# SmartCanBus.net
KiCad netlist of a schematic drawn in Altium Designer
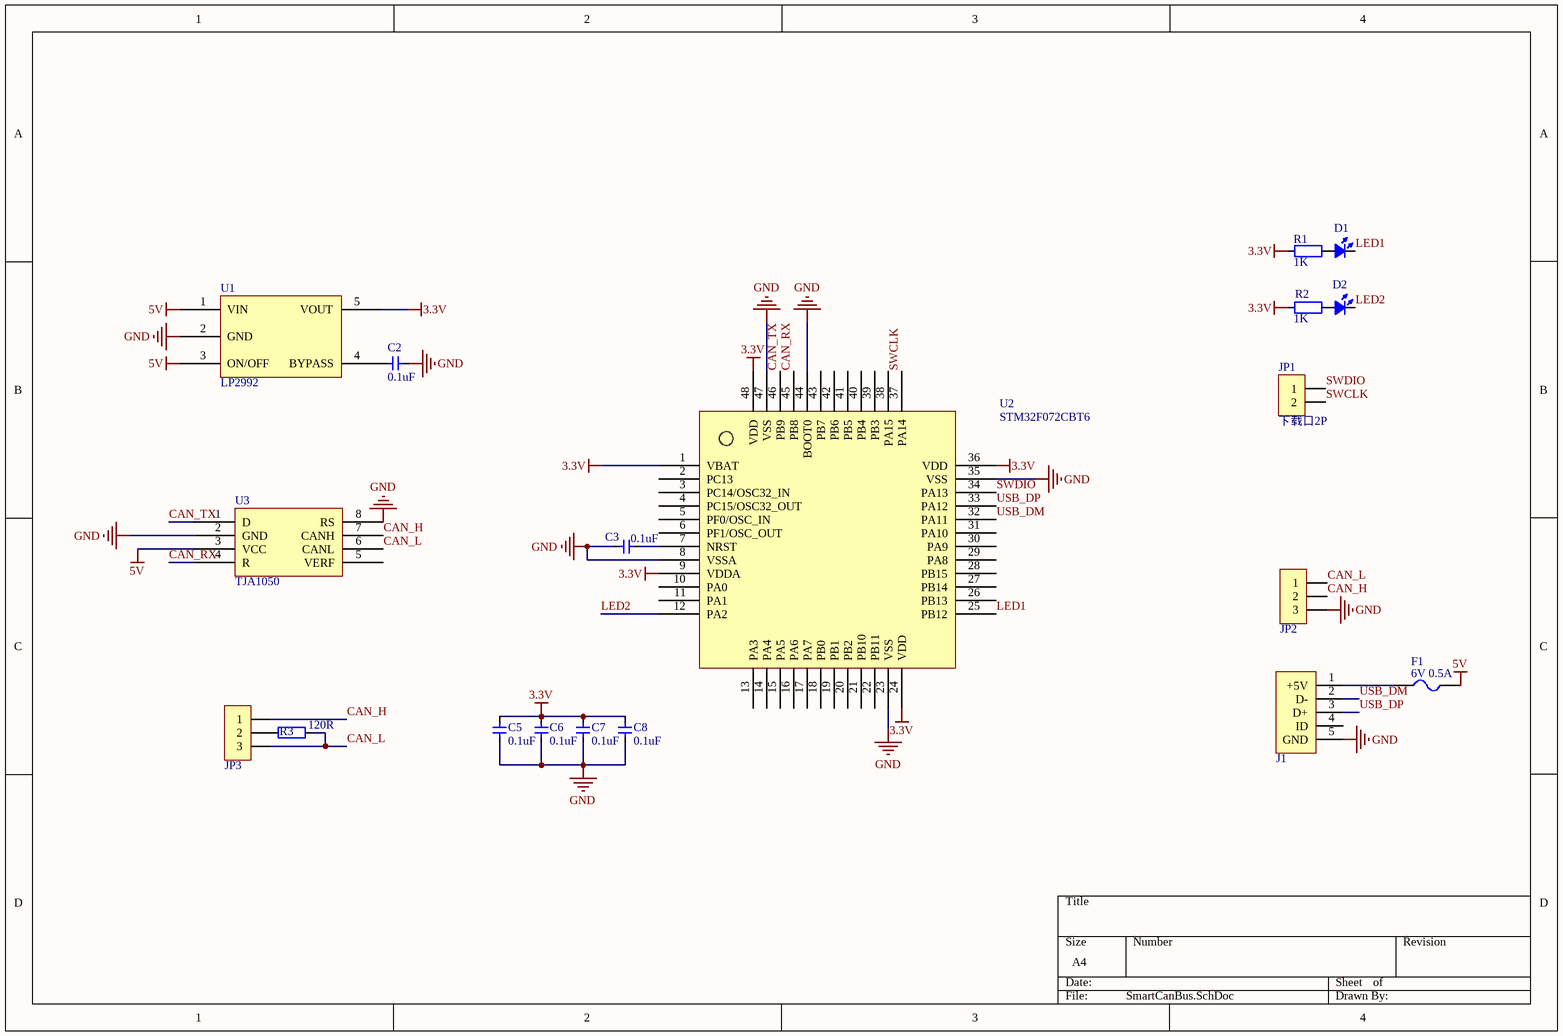
[diagram p0: SmartCanBus.SchDoc]

(export (version "E")
  (design (tool "Eeschema 10.0.6"))
  (components
    (comp (ref "C2")
      (value "0.1uF")
      (footprint "1.00-YltsPcbLib:0603_CAP")
      (description "电容")
      (libsource (lib "0.0 - YltsSchlib") (part "电容-0603"))
    )
    (comp (ref "C3")
      (value "0.1uF")
      (footprint "1.00-YltsPcbLib:0603_CAP")
      (description "电容")
      (libsource (lib "0.0 - YltsSchlib") (part "电容-0603"))
    )
    (comp (ref "C5")
      (value "0.1uF")
      (footprint "1.00-YltsPcbLib:0603_CAP")
      (description "电容")
      (libsource (lib "0.0 - YltsSchlib") (part "电容-0603"))
    )
    (comp (ref "C6")
      (value "0.1uF")
      (footprint "1.00-YltsPcbLib:0603_CAP")
      (description "电容")
      (libsource (lib "0.0 - YltsSchlib") (part "电容-0603"))
    )
    (comp (ref "C7")
      (value "0.1uF")
      (footprint "1.00-YltsPcbLib:0603_CAP")
      (description "电容")
      (libsource (lib "0.0 - YltsSchlib") (part "电容-0603"))
    )
    (comp (ref "C8")
      (value "0.1uF")
      (footprint "1.00-YltsPcbLib:0603_CAP")
      (description "电容")
      (libsource (lib "0.0 - YltsSchlib") (part "电容-0603"))
    )
    (comp (ref "D1")
      (value "LED-0603")
      (footprint "1.00-YltsPcbLib:0603_LED_RED")
      (description "发光二极管")
      (libsource (lib "0.0 - YltsSchlib") (part "二极管-0603-RED"))
    )
    (comp (ref "D2")
      (value "LED-0603")
      (footprint "1.00-YltsPcbLib:0603_LED_BLUE")
      (description "发光二极管")
      (libsource (lib "0.0 - YltsSchlib") (part "二极管-0603-BLUE"))
    )
    (comp (ref "F1")
      (value "6V 0.5A")
      (footprint "FU 0805")
      (description "贴片保险丝")
      (fields (field (name "版权归属") "封装库来自淘宝卖家 ID：黄晶宝石"))
      (libsource (lib "2.0 - 保险丝-晶振-光耦") (part "FU"))
    )
    (comp (ref "J1")
      (value "PowerJack_2.5")
      (footprint "USB-MICRO-B-5P")
      (description "DC Power Jack")
      (libsource (lib "0.0 - YltsSchlib") (part "接插件-USB-MICRO-B"))
    )
    (comp (ref "JP1")
      (value "下载口2P")
      (footprint "下载口2P")
      (description "下载口2P SWD")
      (libsource (lib "0.0 - YltsSchlib") (part "接插件-下载口2P"))
    )
    (comp (ref "JP2")
      (value "HDR-1X3")
      (footprint "KF128-3.81-3P")
      (description "3P接插件")
      (fields (field (name "版权归属") "封装库来自淘宝 ID：黄晶宝石"))
      (libsource (lib "5.5 - 接插件-脚距3.81 (150mil) ") (part "Header 3"))
    )
    (comp (ref "JP3")
      (value "HDR-1X3")
      (footprint "HDR2.54-LI-3P")
      (description "3P接插件")
      (fields (field (name "版权归属") "封装库来自淘宝 ID：黄晶宝石"))
      (libsource (lib "5.3 - 接插件-脚距2.54 (100mil) ") (part "Header 3"))
    )
    (comp (ref "R1")
      (value "1K")
      (footprint "1.00-YltsPcbLib:0603_RES")
      (description "电阻")
      (libsource (lib "0.0 - YltsSchlib") (part "电阻-0603"))
    )
    (comp (ref "R2")
      (value "1K")
      (footprint "1.00-YltsPcbLib:0603_RES")
      (description "电阻")
      (libsource (lib "0.0 - YltsSchlib") (part "电阻-0603"))
    )
    (comp (ref "R3")
      (value "120R")
      (footprint "1.00-YltsPcbLib:0603_RES")
      (description "电阻")
      (fields (field (name "Comment") "1K"))
      (libsource (lib "0.0 - YltsSchlib") (part "电阻-0603"))
    )
    (comp (ref "U1")
      (value "LP2992")
      (footprint "SOT23-5N")
      (description "电源芯片")
      (libsource (lib "MySchlib") (part "LP2992"))
    )
    (comp (ref "U2")
      (value "STM32F072CBT6")
      (footprint "LQFP-48")
      (description "48MHZ Crotex-M0 32位单片机 LQFP-48_7x7x05P")
      (libsource (lib "0.0 - YltsSchlib") (part "STM32F072CBT6"))
    )
    (comp (ref "U3")
      (value "TJA1050")
      (footprint "SOIC-8 - duplicate")
      (description "CAN芯片")
      (libsource (lib "0.0 - YltsSchlib") (part "TJA1050"))
    )
  )
  (nets
    (net (code "1") (name "/CAN_H") (class "Default")
      (node (ref "JP2") (pin "2") (pinfunction "2_2") (pintype "passive"))
      (node (ref "JP3") (pin "1") (pinfunction "1_1") (pintype "passive"))
      (node (ref "U3") (pin "7") (pinfunction "CANH_7") (pintype "passive"))
    )
    (net (code "2") (name "/CAN_L") (class "Default")
      (node (ref "JP2") (pin "1") (pinfunction "1_1") (pintype "passive"))
      (node (ref "JP3") (pin "3") (pinfunction "3_3") (pintype "passive"))
      (node (ref "R3") (pin "2") (pinfunction "2_2") (pintype "passive"))
      (node (ref "U3") (pin "6") (pinfunction "CANL_6") (pintype "passive"))
    )
    (net (code "3") (name "/CAN_RX") (class "Default")
      (node (ref "U2") (pin "45") (pinfunction "PB8_45") (pintype "passive"))
      (node (ref "U3") (pin "4") (pinfunction "R_4") (pintype "passive"))
    )
    (net (code "4") (name "/CAN_TX") (class "Default")
      (node (ref "U2") (pin "46") (pinfunction "PB9_46") (pintype "passive"))
      (node (ref "U3") (pin "1") (pinfunction "D_1") (pintype "passive"))
    )
    (net (code "5") (name "/LED1") (class "Default")
      (node (ref "D1") (pin "2") (pinfunction "K_2") (pintype "passive"))
      (node (ref "U2") (pin "25") (pinfunction "PB12_25") (pintype "passive"))
    )
    (net (code "6") (name "/LED2") (class "Default")
      (node (ref "D2") (pin "2") (pinfunction "K_2") (pintype "passive"))
      (node (ref "U2") (pin "12") (pinfunction "PA2_12") (pintype "passive"))
    )
    (net (code "7") (name "/SWCLK") (class "Default")
      (node (ref "JP1") (pin "2") (pinfunction "2_2") (pintype "passive"))
      (node (ref "U2") (pin "37") (pinfunction "PA14_37") (pintype "passive"))
    )
    (net (code "8") (name "/SWDIO") (class "Default")
      (node (ref "JP1") (pin "1") (pinfunction "1_1") (pintype "passive"))
      (node (ref "U2") (pin "34") (pinfunction "PA13_34") (pintype "passive"))
    )
    (net (code "9") (name "/USB_DM") (class "Default")
      (node (ref "J1") (pin "2") (pinfunction "D-_2") (pintype "passive"))
      (node (ref "U2") (pin "32") (pinfunction "PA11_32") (pintype "passive"))
    )
    (net (code "10") (name "/USB_DP") (class "Default")
      (node (ref "J1") (pin "3") (pinfunction "D+_3") (pintype "passive"))
      (node (ref "U2") (pin "33") (pinfunction "PA12_33") (pintype "passive"))
    )
    (net (code "11") (name "3.3V") (class "Default")
      (node (ref "C5") (pin "1") (pinfunction "1_1") (pintype "passive"))
      (node (ref "C6") (pin "1") (pinfunction "1_1") (pintype "passive"))
      (node (ref "C7") (pin "1") (pinfunction "1_1") (pintype "passive"))
      (node (ref "C8") (pin "1") (pinfunction "1_1") (pintype "passive"))
      (node (ref "R1") (pin "1") (pinfunction "1_1") (pintype "passive"))
      (node (ref "R2") (pin "1") (pinfunction "1_1") (pintype "passive"))
      (node (ref "U1") (pin "5") (pinfunction "VOUT_5") (pintype "passive"))
      (node (ref "U2") (pin "1") (pinfunction "VBAT_1") (pintype "passive"))
      (node (ref "U2") (pin "24") (pinfunction "VDD_24") (pintype "passive"))
      (node (ref "U2") (pin "36") (pinfunction "VDD_36") (pintype "passive"))
      (node (ref "U2") (pin "48") (pinfunction "VDD_48") (pintype "passive"))
      (node (ref "U2") (pin "9") (pinfunction "VDDA_9") (pintype "passive"))
    )
    (net (code "12") (name "5V") (class "Default")
      (node (ref "F1") (pin "2") (pinfunction "2_2") (pintype "passive"))
      (node (ref "U1") (pin "1") (pinfunction "VIN_1") (pintype "passive"))
      (node (ref "U1") (pin "3") (pinfunction "ON/OFF_3") (pintype "passive"))
      (node (ref "U3") (pin "3") (pinfunction "VCC_3") (pintype "passive"))
    )
    (net (code "13") (name "GND") (class "Default")
      (node (ref "C2") (pin "1") (pinfunction "1_1") (pintype "passive"))
      (node (ref "C3") (pin "1") (pinfunction "1_1") (pintype "passive"))
      (node (ref "C5") (pin "2") (pinfunction "2_2") (pintype "passive"))
      (node (ref "C6") (pin "2") (pinfunction "2_2") (pintype "passive"))
      (node (ref "C7") (pin "2") (pinfunction "2_2") (pintype "passive"))
      (node (ref "C8") (pin "2") (pinfunction "2_2") (pintype "passive"))
      (node (ref "J1") (pin "5") (pinfunction "GND_5") (pintype "passive"))
      (node (ref "JP2") (pin "3") (pinfunction "3_3") (pintype "passive"))
      (node (ref "U1") (pin "2") (pinfunction "GND_2") (pintype "passive"))
      (node (ref "U2") (pin "23") (pinfunction "VSS_23") (pintype "passive"))
      (node (ref "U2") (pin "35") (pinfunction "VSS_35") (pintype "passive"))
      (node (ref "U2") (pin "44") (pinfunction "BOOT0_44") (pintype "passive"))
      (node (ref "U2") (pin "47") (pinfunction "VSS_47") (pintype "passive"))
      (node (ref "U2") (pin "8") (pinfunction "VSSA_8") (pintype "passive"))
      (node (ref "U3") (pin "2") (pinfunction "GND_2") (pintype "passive"))
      (node (ref "U3") (pin "8") (pinfunction "RS_8") (pintype "passive"))
    )
    (net (code "14") (name "Net-(D1-A)") (class "Default")
      (node (ref "D1") (pin "1") (pinfunction "A_1") (pintype "passive"))
      (node (ref "R1") (pin "2") (pinfunction "2_2") (pintype "passive"))
    )
    (net (code "15") (name "Net-(D2-A)") (class "Default")
      (node (ref "D2") (pin "1") (pinfunction "A_1") (pintype "passive"))
      (node (ref "R2") (pin "2") (pinfunction "2_2") (pintype "passive"))
    )
    (net (code "16") (name "Net-(J1-+5V)") (class "Default")
      (node (ref "F1") (pin "1") (pinfunction "1_1") (pintype "passive"))
      (node (ref "J1") (pin "1") (pinfunction "+5V_1") (pintype "passive"))
    )
    (net (code "17") (name "Net-(JP3-Pad2)") (class "Default")
      (node (ref "JP3") (pin "2") (pinfunction "2_2") (pintype "passive"))
      (node (ref "R3") (pin "1") (pinfunction "1_1") (pintype "passive"))
    )
    (net (code "18") (name "Net-(U1-BYPASS)") (class "Default")
      (node (ref "C2") (pin "2") (pinfunction "2_2") (pintype "passive"))
      (node (ref "U1") (pin "4") (pinfunction "BYPASS_4") (pintype "passive"))
    )
    (net (code "19") (name "Net-(U2-NRST)") (class "Default")
      (node (ref "C3") (pin "2") (pinfunction "2_2") (pintype "passive"))
      (node (ref "U2") (pin "7") (pinfunction "NRST_7") (pintype "passive"))
    )
    (net (code "20") (name "unconnected-(J1-ID-Pad4)") (class "Default")
      (node (ref "J1") (pin "4") (pinfunction "ID_4") (pintype "passive"))
    )
    (net (code "21") (name "unconnected-(U2-PA0-Pad10)") (class "Default")
      (node (ref "U2") (pin "10") (pinfunction "PA0_10") (pintype "passive"))
    )
    (net (code "22") (name "unconnected-(U2-PA1-Pad11)") (class "Default")
      (node (ref "U2") (pin "11") (pinfunction "PA1_11") (pintype "passive"))
    )
    (net (code "23") (name "unconnected-(U2-PA3-Pad13)") (class "Default")
      (node (ref "U2") (pin "13") (pinfunction "PA3_13") (pintype "passive"))
    )
    (net (code "24") (name "unconnected-(U2-PA4-Pad14)") (class "Default")
      (node (ref "U2") (pin "14") (pinfunction "PA4_14") (pintype "passive"))
    )
    (net (code "25") (name "unconnected-(U2-PA5-Pad15)") (class "Default")
      (node (ref "U2") (pin "15") (pinfunction "PA5_15") (pintype "passive"))
    )
    (net (code "26") (name "unconnected-(U2-PA6-Pad16)") (class "Default")
      (node (ref "U2") (pin "16") (pinfunction "PA6_16") (pintype "passive"))
    )
    (net (code "27") (name "unconnected-(U2-PA7-Pad17)") (class "Default")
      (node (ref "U2") (pin "17") (pinfunction "PA7_17") (pintype "passive"))
    )
    (net (code "28") (name "unconnected-(U2-PA8-Pad29)") (class "Default")
      (node (ref "U2") (pin "29") (pinfunction "PA8_29") (pintype "passive"))
    )
    (net (code "29") (name "unconnected-(U2-PA9-Pad30)") (class "Default")
      (node (ref "U2") (pin "30") (pinfunction "PA9_30") (pintype "passive"))
    )
    (net (code "30") (name "unconnected-(U2-PA10-Pad31)") (class "Default")
      (node (ref "U2") (pin "31") (pinfunction "PA10_31") (pintype "passive"))
    )
    (net (code "31") (name "unconnected-(U2-PA15-Pad38)") (class "Default")
      (node (ref "U2") (pin "38") (pinfunction "PA15_38") (pintype "passive"))
    )
    (net (code "32") (name "unconnected-(U2-PB0-Pad18)") (class "Default")
      (node (ref "U2") (pin "18") (pinfunction "PB0_18") (pintype "passive"))
    )
    (net (code "33") (name "unconnected-(U2-PB1-Pad19)") (class "Default")
      (node (ref "U2") (pin "19") (pinfunction "PB1_19") (pintype "passive"))
    )
    (net (code "34") (name "unconnected-(U2-PB2-Pad20)") (class "Default")
      (node (ref "U2") (pin "20") (pinfunction "PB2_20") (pintype "passive"))
    )
    (net (code "35") (name "unconnected-(U2-PB3-Pad39)") (class "Default")
      (node (ref "U2") (pin "39") (pinfunction "PB3_39") (pintype "passive"))
    )
    (net (code "36") (name "unconnected-(U2-PB4-Pad40)") (class "Default")
      (node (ref "U2") (pin "40") (pinfunction "PB4_40") (pintype "passive"))
    )
    (net (code "37") (name "unconnected-(U2-PB5-Pad41)") (class "Default")
      (node (ref "U2") (pin "41") (pinfunction "PB5_41") (pintype "passive"))
    )
    (net (code "38") (name "unconnected-(U2-PB6-Pad42)") (class "Default")
      (node (ref "U2") (pin "42") (pinfunction "PB6_42") (pintype "passive"))
    )
    (net (code "39") (name "unconnected-(U2-PB7-Pad43)") (class "Default")
      (node (ref "U2") (pin "43") (pinfunction "PB7_43") (pintype "passive"))
    )
    (net (code "40") (name "unconnected-(U2-PB10-Pad21)") (class "Default")
      (node (ref "U2") (pin "21") (pinfunction "PB10_21") (pintype "passive"))
    )
    (net (code "41") (name "unconnected-(U2-PB11-Pad22)") (class "Default")
      (node (ref "U2") (pin "22") (pinfunction "PB11_22") (pintype "passive"))
    )
    (net (code "42") (name "unconnected-(U2-PB13-Pad26)") (class "Default")
      (node (ref "U2") (pin "26") (pinfunction "PB13_26") (pintype "passive"))
    )
    (net (code "43") (name "unconnected-(U2-PB14-Pad27)") (class "Default")
      (node (ref "U2") (pin "27") (pinfunction "PB14_27") (pintype "passive"))
    )
    (net (code "44") (name "unconnected-(U2-PB15-Pad28)") (class "Default")
      (node (ref "U2") (pin "28") (pinfunction "PB15_28") (pintype "passive"))
    )
    (net (code "45") (name "unconnected-(U2-PC13-Pad2)") (class "Default")
      (node (ref "U2") (pin "2") (pinfunction "PC13_2") (pintype "passive"))
    )
    (net (code "46") (name "unconnected-(U2-PC14{slash}OSC32_IN-Pad3)") (class "Default")
      (node (ref "U2") (pin "3") (pinfunction "PC14/OSC32_IN_3") (pintype "passive"))
    )
    (net (code "47") (name "unconnected-(U2-PC15{slash}OSC32_OUT-Pad4)") (class "Default")
      (node (ref "U2") (pin "4") (pinfunction "PC15/OSC32_OUT_4") (pintype "passive"))
    )
    (net (code "48") (name "unconnected-(U2-PF0{slash}OSC_IN-Pad5)") (class "Default")
      (node (ref "U2") (pin "5") (pinfunction "PF0/OSC_IN_5") (pintype "passive"))
    )
    (net (code "49") (name "unconnected-(U2-PF1{slash}OSC_OUT-Pad6)") (class "Default")
      (node (ref "U2") (pin "6") (pinfunction "PF1/OSC_OUT_6") (pintype "passive"))
    )
    (net (code "50") (name "unconnected-(U3-VERF-Pad5)") (class "Default")
      (node (ref "U3") (pin "5") (pinfunction "VERF_5") (pintype "passive"))
    )
  )
)
